# Sheet4.net
KiCad netlist of a schematic drawn in Altium Designer
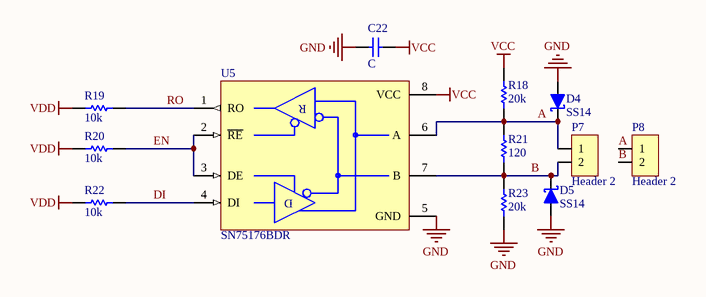
[diagram p0: Sheet4.SchDoc]

(export (version "E")
  (design (tool "Eeschema 10.0.6"))
  (components
    (comp (ref "C22")
      (value "C")
      (footprint "C 0805 (2012)")
      (description "Capacitor non-pol")
      (libsource (lib "BKIT4U_LIB") (part "Capacitor NP"))
    )
    (comp (ref "D4")
      (value "SS14")
      (footprint "DO-214AC (SMA)")
      (description "Schottky Diode")
      (fields (field (name "PUBLISHER") "Altium Limited"))
      (libsource (lib "BKIT4U_LIB") (part "Diode Schottky"))
    )
    (comp (ref "D5")
      (value "SS14")
      (footprint "DO-214AC (SMA)")
      (description "Schottky Diode")
      (fields (field (name "PUBLISHER") "Altium Limited"))
      (libsource (lib "BKIT4U_LIB") (part "Diode Schottky"))
    )
    (comp (ref "P7")
      (value "Header 2")
      (footprint "HDR Domino 2")
      (description "Header, 2-Pin")
      (fields (field (name "PUBLISHER") "Altium Limited"))
      (libsource (lib "BKIT4U_LIB") (part "Header 2"))
    )
    (comp (ref "P8")
      (value "Header 2")
      (footprint "HDR Domino 2")
      (description "Header, 2-Pin")
      (fields (field (name "PUBLISHER") "Altium Limited"))
      (libsource (lib "BKIT4U_LIB") (part "Header 2"))
    )
    (comp (ref "R18")
      (value "20k")
      (footprint "R 0805 (2012)")
      (description "Resistor")
      (fields (field (name "PUBLISHER") "Altium Limited"))
      (libsource (lib "BKIT4U_LIB") (part "Resistor"))
    )
    (comp (ref "R19")
      (value "10k")
      (footprint "R 0805 (2012)")
      (description "Resistor")
      (fields (field (name "PUBLISHER") "Altium Limited"))
      (libsource (lib "BKIT4U_LIB") (part "Resistor"))
    )
    (comp (ref "R20")
      (value "10k")
      (footprint "R 0805 (2012)")
      (description "Resistor")
      (fields (field (name "PUBLISHER") "Altium Limited"))
      (libsource (lib "BKIT4U_LIB") (part "Resistor"))
    )
    (comp (ref "R21")
      (value "120")
      (footprint "R 0805 (2012)")
      (description "Resistor")
      (fields (field (name "PUBLISHER") "Altium Limited"))
      (libsource (lib "BKIT4U_LIB") (part "Resistor"))
    )
    (comp (ref "R22")
      (value "10k")
      (footprint "R 0805 (2012)")
      (description "Resistor")
      (fields (field (name "PUBLISHER") "Altium Limited"))
      (libsource (lib "BKIT4U_LIB") (part "Resistor"))
    )
    (comp (ref "R23")
      (value "20k")
      (footprint "R 0805 (2012)")
      (description "Resistor")
      (fields (field (name "PUBLISHER") "Altium Limited"))
      (libsource (lib "BKIT4U_LIB") (part "Resistor"))
    )
    (comp (ref "U5") (value "SN75176BDR") (footprint "SOIC-8") (libsource (lib "BKIT4U_LIB") (part "MAX485")))
  )
  (nets
    (net (code "1") (name "/A") (class "Default")
      (node (ref "D4") (pin "2") (pinfunction "K_2") (pintype "passive"))
      (node (ref "P7") (pin "1") (pinfunction "1_1") (pintype "passive"))
      (node (ref "P8") (pin "1") (pinfunction "1_1") (pintype "passive"))
      (node (ref "R18") (pin "1") (pinfunction "1_1") (pintype "passive"))
      (node (ref "R21") (pin "2") (pinfunction "2_2") (pintype "passive"))
      (node (ref "U5") (pin "6") (pinfunction "A_6") (pintype "passive"))
    )
    (net (code "2") (name "/B") (class "Default")
      (node (ref "D5") (pin "2") (pinfunction "K_2") (pintype "passive"))
      (node (ref "P7") (pin "2") (pinfunction "2_2") (pintype "passive"))
      (node (ref "P8") (pin "2") (pinfunction "2_2") (pintype "passive"))
      (node (ref "R21") (pin "1") (pinfunction "1_1") (pintype "passive"))
      (node (ref "R23") (pin "2") (pinfunction "2_2") (pintype "passive"))
      (node (ref "U5") (pin "7") (pinfunction "B_7") (pintype "passive"))
    )
    (net (code "3") (name "/DI") (class "Default")
      (node (ref "R22") (pin "1") (pinfunction "1_1") (pintype "passive"))
      (node (ref "U5") (pin "4") (pinfunction "DI_4") (pintype "input"))
    )
    (net (code "4") (name "/EN") (class "Default")
      (node (ref "R20") (pin "1") (pinfunction "1_1") (pintype "passive"))
      (node (ref "U5") (pin "2") (pinfunction "~{RE}_2") (pintype "input"))
      (node (ref "U5") (pin "3") (pinfunction "DE_3") (pintype "input"))
    )
    (net (code "5") (name "/RO") (class "Default")
      (node (ref "R19") (pin "1") (pinfunction "1_1") (pintype "passive"))
      (node (ref "U5") (pin "1") (pinfunction "RO_1") (pintype "output"))
    )
    (net (code "6") (name "GND") (class "Default")
      (node (ref "C22") (pin "2") (pinfunction "2_2") (pintype "passive"))
      (node (ref "D4") (pin "1") (pinfunction "A_1") (pintype "passive"))
      (node (ref "D5") (pin "1") (pinfunction "A_1") (pintype "passive"))
      (node (ref "R23") (pin "1") (pinfunction "1_1") (pintype "passive"))
      (node (ref "U5") (pin "5") (pinfunction "GND_5") (pintype "power_in"))
    )
    (net (code "7") (name "VCC") (class "Default")
      (node (ref "C22") (pin "1") (pinfunction "1_1") (pintype "passive"))
      (node (ref "R18") (pin "2") (pinfunction "2_2") (pintype "passive"))
      (node (ref "U5") (pin "8") (pinfunction "VCC_8") (pintype "passive"))
    )
    (net (code "8") (name "VDD") (class "Default")
      (node (ref "R19") (pin "2") (pinfunction "2_2") (pintype "passive"))
      (node (ref "R20") (pin "2") (pinfunction "2_2") (pintype "passive"))
      (node (ref "R22") (pin "2") (pinfunction "2_2") (pintype "passive"))
    )
  )
)
